# Sheet1.net
KiCad netlist of a schematic drawn in Altium Designer
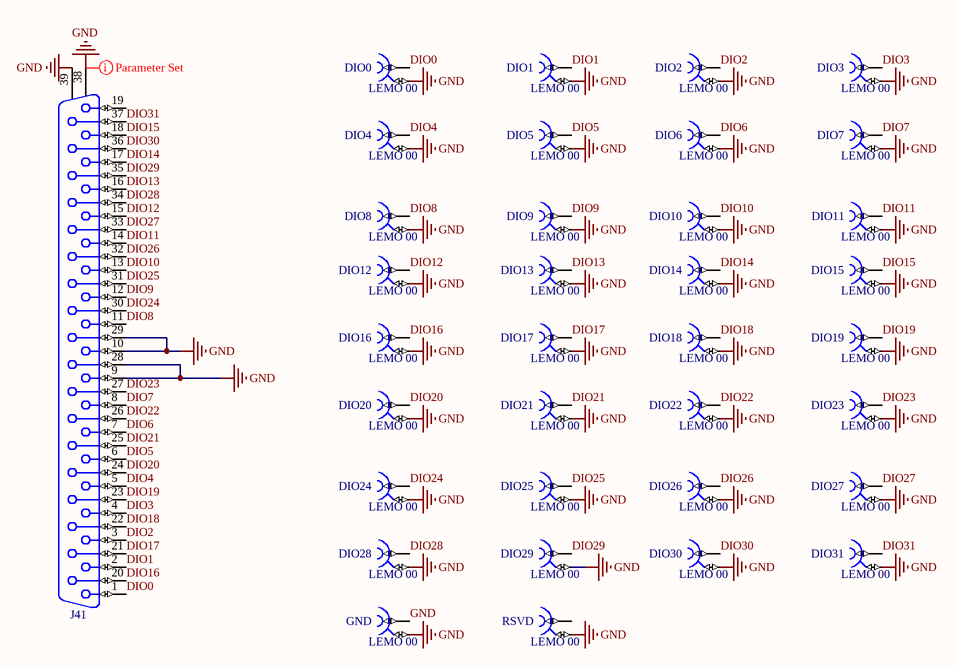
[diagram p0: Sheet1.SchDoc]

(export (version "E")
  (design (tool "Eeschema 10.0.6"))
  (components
    (comp (ref "DIO0")
      (value "LEMO 00")
      (footprint "LEMO_EPA.00.250.NTN")
      (fields
        (field (name "PART NUMBER") "LEMO_EPA.00.250.NTN")
        (field (name "MANUFACTURER") "LEMO")
        (field (name "MANUFACTURER PART NUMBER") "EPA.00.250.NTN")
        (field (name "AUTHOR") "CERN DEM JLC")
      )
      (libsource (lib "Connectors") (part "Coax_1Female_1Shield"))
    )
    (comp (ref "DIO1")
      (value "LEMO 00")
      (footprint "LEMO_EPA.00.250.NTN")
      (fields
        (field (name "PART NUMBER") "LEMO_EPA.00.250.NTN")
        (field (name "MANUFACTURER") "LEMO")
        (field (name "MANUFACTURER PART NUMBER") "EPA.00.250.NTN")
        (field (name "AUTHOR") "CERN DEM JLC")
      )
      (libsource (lib "Connectors") (part "Coax_1Female_1Shield"))
    )
    (comp (ref "DIO2")
      (value "LEMO 00")
      (footprint "LEMO_EPA.00.250.NTN")
      (fields
        (field (name "PART NUMBER") "LEMO_EPA.00.250.NTN")
        (field (name "MANUFACTURER") "LEMO")
        (field (name "MANUFACTURER PART NUMBER") "EPA.00.250.NTN")
        (field (name "AUTHOR") "CERN DEM JLC")
      )
      (libsource (lib "Connectors") (part "Coax_1Female_1Shield"))
    )
    (comp (ref "DIO3")
      (value "LEMO 00")
      (footprint "LEMO_EPA.00.250.NTN")
      (fields
        (field (name "PART NUMBER") "LEMO_EPA.00.250.NTN")
        (field (name "MANUFACTURER") "LEMO")
        (field (name "MANUFACTURER PART NUMBER") "EPA.00.250.NTN")
        (field (name "AUTHOR") "CERN DEM JLC")
      )
      (libsource (lib "Connectors") (part "Coax_1Female_1Shield"))
    )
    (comp (ref "DIO4")
      (value "LEMO 00")
      (footprint "LEMO_EPA.00.250.NTN")
      (fields
        (field (name "PART NUMBER") "LEMO_EPA.00.250.NTN")
        (field (name "MANUFACTURER") "LEMO")
        (field (name "MANUFACTURER PART NUMBER") "EPA.00.250.NTN")
        (field (name "AUTHOR") "CERN DEM JLC")
      )
      (libsource (lib "Connectors") (part "Coax_1Female_1Shield"))
    )
    (comp (ref "DIO5")
      (value "LEMO 00")
      (footprint "LEMO_EPA.00.250.NTN")
      (fields
        (field (name "PART NUMBER") "LEMO_EPA.00.250.NTN")
        (field (name "MANUFACTURER") "LEMO")
        (field (name "MANUFACTURER PART NUMBER") "EPA.00.250.NTN")
        (field (name "AUTHOR") "CERN DEM JLC")
      )
      (libsource (lib "Connectors") (part "Coax_1Female_1Shield"))
    )
    (comp (ref "DIO6")
      (value "LEMO 00")
      (footprint "LEMO_EPA.00.250.NTN")
      (fields
        (field (name "PART NUMBER") "LEMO_EPA.00.250.NTN")
        (field (name "MANUFACTURER") "LEMO")
        (field (name "MANUFACTURER PART NUMBER") "EPA.00.250.NTN")
        (field (name "AUTHOR") "CERN DEM JLC")
      )
      (libsource (lib "Connectors") (part "Coax_1Female_1Shield"))
    )
    (comp (ref "DIO7")
      (value "LEMO 00")
      (footprint "LEMO_EPA.00.250.NTN")
      (fields
        (field (name "PART NUMBER") "LEMO_EPA.00.250.NTN")
        (field (name "MANUFACTURER") "LEMO")
        (field (name "MANUFACTURER PART NUMBER") "EPA.00.250.NTN")
        (field (name "AUTHOR") "CERN DEM JLC")
      )
      (libsource (lib "Connectors") (part "Coax_1Female_1Shield"))
    )
    (comp (ref "DIO8")
      (value "LEMO 00")
      (footprint "LEMO_EPA.00.250.NTN")
      (fields
        (field (name "PART NUMBER") "LEMO_EPA.00.250.NTN")
        (field (name "MANUFACTURER") "LEMO")
        (field (name "MANUFACTURER PART NUMBER") "EPA.00.250.NTN")
        (field (name "AUTHOR") "CERN DEM JLC")
      )
      (libsource (lib "Connectors") (part "Coax_1Female_1Shield"))
    )
    (comp (ref "DIO9")
      (value "LEMO 00")
      (footprint "LEMO_EPA.00.250.NTN")
      (fields
        (field (name "PART NUMBER") "LEMO_EPA.00.250.NTN")
        (field (name "MANUFACTURER") "LEMO")
        (field (name "MANUFACTURER PART NUMBER") "EPA.00.250.NTN")
        (field (name "AUTHOR") "CERN DEM JLC")
      )
      (libsource (lib "Connectors") (part "Coax_1Female_1Shield"))
    )
    (comp (ref "DIO10")
      (value "LEMO 00")
      (footprint "LEMO_EPA.00.250.NTN")
      (fields
        (field (name "PART NUMBER") "LEMO_EPA.00.250.NTN")
        (field (name "MANUFACTURER") "LEMO")
        (field (name "MANUFACTURER PART NUMBER") "EPA.00.250.NTN")
        (field (name "AUTHOR") "CERN DEM JLC")
      )
      (libsource (lib "Connectors") (part "Coax_1Female_1Shield"))
    )
    (comp (ref "DIO11")
      (value "LEMO 00")
      (footprint "LEMO_EPA.00.250.NTN")
      (fields
        (field (name "PART NUMBER") "LEMO_EPA.00.250.NTN")
        (field (name "MANUFACTURER") "LEMO")
        (field (name "MANUFACTURER PART NUMBER") "EPA.00.250.NTN")
        (field (name "AUTHOR") "CERN DEM JLC")
      )
      (libsource (lib "Connectors") (part "Coax_1Female_1Shield"))
    )
    (comp (ref "DIO12")
      (value "LEMO 00")
      (footprint "LEMO_EPA.00.250.NTN")
      (fields
        (field (name "PART NUMBER") "LEMO_EPA.00.250.NTN")
        (field (name "MANUFACTURER") "LEMO")
        (field (name "MANUFACTURER PART NUMBER") "EPA.00.250.NTN")
        (field (name "AUTHOR") "CERN DEM JLC")
      )
      (libsource (lib "Connectors") (part "Coax_1Female_1Shield"))
    )
    (comp (ref "DIO13")
      (value "LEMO 00")
      (footprint "LEMO_EPA.00.250.NTN")
      (fields
        (field (name "PART NUMBER") "LEMO_EPA.00.250.NTN")
        (field (name "MANUFACTURER") "LEMO")
        (field (name "MANUFACTURER PART NUMBER") "EPA.00.250.NTN")
        (field (name "AUTHOR") "CERN DEM JLC")
      )
      (libsource (lib "Connectors") (part "Coax_1Female_1Shield"))
    )
    (comp (ref "DIO14")
      (value "LEMO 00")
      (footprint "LEMO_EPA.00.250.NTN")
      (fields
        (field (name "PART NUMBER") "LEMO_EPA.00.250.NTN")
        (field (name "MANUFACTURER") "LEMO")
        (field (name "MANUFACTURER PART NUMBER") "EPA.00.250.NTN")
        (field (name "AUTHOR") "CERN DEM JLC")
      )
      (libsource (lib "Connectors") (part "Coax_1Female_1Shield"))
    )
    (comp (ref "DIO15")
      (value "LEMO 00")
      (footprint "LEMO_EPA.00.250.NTN")
      (fields
        (field (name "PART NUMBER") "LEMO_EPA.00.250.NTN")
        (field (name "MANUFACTURER") "LEMO")
        (field (name "MANUFACTURER PART NUMBER") "EPA.00.250.NTN")
        (field (name "AUTHOR") "CERN DEM JLC")
      )
      (libsource (lib "Connectors") (part "Coax_1Female_1Shield"))
    )
    (comp (ref "DIO16")
      (value "LEMO 00")
      (footprint "LEMO_EPA.00.250.NTN")
      (fields
        (field (name "PART NUMBER") "LEMO_EPA.00.250.NTN")
        (field (name "MANUFACTURER") "LEMO")
        (field (name "MANUFACTURER PART NUMBER") "EPA.00.250.NTN")
        (field (name "AUTHOR") "CERN DEM JLC")
      )
      (libsource (lib "Connectors") (part "Coax_1Female_1Shield"))
    )
    (comp (ref "DIO17")
      (value "LEMO 00")
      (footprint "LEMO_EPA.00.250.NTN")
      (fields
        (field (name "PART NUMBER") "LEMO_EPA.00.250.NTN")
        (field (name "MANUFACTURER") "LEMO")
        (field (name "MANUFACTURER PART NUMBER") "EPA.00.250.NTN")
        (field (name "AUTHOR") "CERN DEM JLC")
      )
      (libsource (lib "Connectors") (part "Coax_1Female_1Shield"))
    )
    (comp (ref "DIO18")
      (value "LEMO 00")
      (footprint "LEMO_EPA.00.250.NTN")
      (fields
        (field (name "PART NUMBER") "LEMO_EPA.00.250.NTN")
        (field (name "MANUFACTURER") "LEMO")
        (field (name "MANUFACTURER PART NUMBER") "EPA.00.250.NTN")
        (field (name "AUTHOR") "CERN DEM JLC")
      )
      (libsource (lib "Connectors") (part "Coax_1Female_1Shield"))
    )
    (comp (ref "DIO19")
      (value "LEMO 00")
      (footprint "LEMO_EPA.00.250.NTN")
      (fields
        (field (name "PART NUMBER") "LEMO_EPA.00.250.NTN")
        (field (name "MANUFACTURER") "LEMO")
        (field (name "MANUFACTURER PART NUMBER") "EPA.00.250.NTN")
        (field (name "AUTHOR") "CERN DEM JLC")
      )
      (libsource (lib "Connectors") (part "Coax_1Female_1Shield"))
    )
    (comp (ref "DIO20")
      (value "LEMO 00")
      (footprint "LEMO_EPA.00.250.NTN")
      (fields
        (field (name "PART NUMBER") "LEMO_EPA.00.250.NTN")
        (field (name "MANUFACTURER") "LEMO")
        (field (name "MANUFACTURER PART NUMBER") "EPA.00.250.NTN")
        (field (name "AUTHOR") "CERN DEM JLC")
      )
      (libsource (lib "Connectors") (part "Coax_1Female_1Shield"))
    )
    (comp (ref "DIO21")
      (value "LEMO 00")
      (footprint "LEMO_EPA.00.250.NTN")
      (fields
        (field (name "PART NUMBER") "LEMO_EPA.00.250.NTN")
        (field (name "MANUFACTURER") "LEMO")
        (field (name "MANUFACTURER PART NUMBER") "EPA.00.250.NTN")
        (field (name "AUTHOR") "CERN DEM JLC")
      )
      (libsource (lib "Connectors") (part "Coax_1Female_1Shield"))
    )
    (comp (ref "DIO22")
      (value "LEMO 00")
      (footprint "LEMO_EPA.00.250.NTN")
      (fields
        (field (name "PART NUMBER") "LEMO_EPA.00.250.NTN")
        (field (name "MANUFACTURER") "LEMO")
        (field (name "MANUFACTURER PART NUMBER") "EPA.00.250.NTN")
        (field (name "AUTHOR") "CERN DEM JLC")
      )
      (libsource (lib "Connectors") (part "Coax_1Female_1Shield"))
    )
    (comp (ref "DIO23")
      (value "LEMO 00")
      (footprint "LEMO_EPA.00.250.NTN")
      (fields
        (field (name "PART NUMBER") "LEMO_EPA.00.250.NTN")
        (field (name "MANUFACTURER") "LEMO")
        (field (name "MANUFACTURER PART NUMBER") "EPA.00.250.NTN")
        (field (name "AUTHOR") "CERN DEM JLC")
      )
      (libsource (lib "Connectors") (part "Coax_1Female_1Shield"))
    )
    (comp (ref "DIO24")
      (value "LEMO 00")
      (footprint "LEMO_EPA.00.250.NTN")
      (fields
        (field (name "PART NUMBER") "LEMO_EPA.00.250.NTN")
        (field (name "MANUFACTURER") "LEMO")
        (field (name "MANUFACTURER PART NUMBER") "EPA.00.250.NTN")
        (field (name "AUTHOR") "CERN DEM JLC")
      )
      (libsource (lib "Connectors") (part "Coax_1Female_1Shield"))
    )
    (comp (ref "DIO25")
      (value "LEMO 00")
      (footprint "LEMO_EPA.00.250.NTN")
      (fields
        (field (name "PART NUMBER") "LEMO_EPA.00.250.NTN")
        (field (name "MANUFACTURER") "LEMO")
        (field (name "MANUFACTURER PART NUMBER") "EPA.00.250.NTN")
        (field (name "AUTHOR") "CERN DEM JLC")
      )
      (libsource (lib "Connectors") (part "Coax_1Female_1Shield"))
    )
    (comp (ref "DIO26")
      (value "LEMO 00")
      (footprint "LEMO_EPA.00.250.NTN")
      (fields
        (field (name "PART NUMBER") "LEMO_EPA.00.250.NTN")
        (field (name "MANUFACTURER") "LEMO")
        (field (name "MANUFACTURER PART NUMBER") "EPA.00.250.NTN")
        (field (name "AUTHOR") "CERN DEM JLC")
      )
      (libsource (lib "Connectors") (part "Coax_1Female_1Shield"))
    )
    (comp (ref "DIO27")
      (value "LEMO 00")
      (footprint "LEMO_EPA.00.250.NTN")
      (fields
        (field (name "PART NUMBER") "LEMO_EPA.00.250.NTN")
        (field (name "MANUFACTURER") "LEMO")
        (field (name "MANUFACTURER PART NUMBER") "EPA.00.250.NTN")
        (field (name "AUTHOR") "CERN DEM JLC")
      )
      (libsource (lib "Connectors") (part "Coax_1Female_1Shield"))
    )
    (comp (ref "DIO28")
      (value "LEMO 00")
      (footprint "LEMO_EPA.00.250.NTN")
      (fields
        (field (name "PART NUMBER") "LEMO_EPA.00.250.NTN")
        (field (name "MANUFACTURER") "LEMO")
        (field (name "MANUFACTURER PART NUMBER") "EPA.00.250.NTN")
        (field (name "AUTHOR") "CERN DEM JLC")
      )
      (libsource (lib "Connectors") (part "Coax_1Female_1Shield"))
    )
    (comp (ref "DIO29")
      (value "LEMO 00")
      (footprint "LEMO_EPA.00.250.NTN")
      (fields
        (field (name "PART NUMBER") "LEMO_EPA.00.250.NTN")
        (field (name "MANUFACTURER") "LEMO")
        (field (name "MANUFACTURER PART NUMBER") "EPA.00.250.NTN")
        (field (name "AUTHOR") "CERN DEM JLC")
      )
      (libsource (lib "Connectors") (part "Coax_1Female_1Shield"))
    )
    (comp (ref "DIO30")
      (value "LEMO 00")
      (footprint "LEMO_EPA.00.250.NTN")
      (fields
        (field (name "PART NUMBER") "LEMO_EPA.00.250.NTN")
        (field (name "MANUFACTURER") "LEMO")
        (field (name "MANUFACTURER PART NUMBER") "EPA.00.250.NTN")
        (field (name "AUTHOR") "CERN DEM JLC")
      )
      (libsource (lib "Connectors") (part "Coax_1Female_1Shield"))
    )
    (comp (ref "DIO31")
      (value "LEMO 00")
      (footprint "LEMO_EPA.00.250.NTN")
      (fields
        (field (name "PART NUMBER") "LEMO_EPA.00.250.NTN")
        (field (name "MANUFACTURER") "LEMO")
        (field (name "MANUFACTURER PART NUMBER") "EPA.00.250.NTN")
        (field (name "AUTHOR") "CERN DEM JLC")
      )
      (libsource (lib "Connectors") (part "Coax_1Female_1Shield"))
    )
    (comp (ref "GND")
      (value "LEMO 00")
      (footprint "LEMO_EPA.00.250.NTN")
      (fields
        (field (name "PART NUMBER") "LEMO_EPA.00.250.NTN")
        (field (name "MANUFACTURER") "LEMO")
        (field (name "MANUFACTURER PART NUMBER") "EPA.00.250.NTN")
        (field (name "AUTHOR") "CERN DEM JLC")
      )
      (libsource (lib "Connectors") (part "Coax_1Female_1Shield"))
    )
    (comp (ref "J41")
      (value "D-SUB37F")
      (footprint "NORCOMP_172-037-242R011")
      (description "Connector D-sub 37 Female")
      (fields
        (field (name "PART NUMBER") "NORCOMP_172-037-242R011")
        (field (name "MANUFACTURER") "NORCOMP")
        (field (name "AUTHOR") "CERN DEM MR")
      )
      (libsource (lib "Connectors") (part "Connector D-sub 37 Female"))
    )
    (comp (ref "RSVD")
      (value "LEMO 00")
      (footprint "LEMO_EPA.00.250.NTN")
      (fields
        (field (name "PART NUMBER") "LEMO_EPA.00.250.NTN")
        (field (name "MANUFACTURER") "LEMO")
        (field (name "MANUFACTURER PART NUMBER") "EPA.00.250.NTN")
        (field (name "AUTHOR") "CERN DEM JLC")
      )
      (libsource (lib "Connectors") (part "Coax_1Female_1Shield"))
    )
  )
  (nets
    (net (code "1") (name "/DIO0") (class "Default")
      (node (ref "DIO0") (pin "1") (pinfunction "1_1") (pintype "bidirectional"))
      (node (ref "J41") (pin "1") (pinfunction "1_1") (pintype "bidirectional"))
    )
    (net (code "2") (name "/DIO1") (class "Default")
      (node (ref "DIO1") (pin "1") (pinfunction "1_1") (pintype "bidirectional"))
      (node (ref "J41") (pin "2") (pinfunction "2_2") (pintype "bidirectional"))
    )
    (net (code "3") (name "/DIO2") (class "Default")
      (node (ref "DIO2") (pin "1") (pinfunction "1_1") (pintype "bidirectional"))
      (node (ref "J41") (pin "3") (pinfunction "3_3") (pintype "bidirectional"))
    )
    (net (code "4") (name "/DIO3") (class "Default")
      (node (ref "DIO3") (pin "1") (pinfunction "1_1") (pintype "bidirectional"))
      (node (ref "J41") (pin "4") (pinfunction "4_4") (pintype "bidirectional"))
    )
    (net (code "5") (name "/DIO4") (class "Default")
      (node (ref "DIO4") (pin "1") (pinfunction "1_1") (pintype "bidirectional"))
      (node (ref "J41") (pin "5") (pinfunction "5_5") (pintype "bidirectional"))
    )
    (net (code "6") (name "/DIO5") (class "Default")
      (node (ref "DIO5") (pin "1") (pinfunction "1_1") (pintype "bidirectional"))
      (node (ref "J41") (pin "6") (pinfunction "6_6") (pintype "bidirectional"))
    )
    (net (code "7") (name "/DIO6") (class "Default")
      (node (ref "DIO6") (pin "1") (pinfunction "1_1") (pintype "bidirectional"))
      (node (ref "J41") (pin "7") (pinfunction "7_7") (pintype "bidirectional"))
    )
    (net (code "8") (name "/DIO7") (class "Default")
      (node (ref "DIO7") (pin "1") (pinfunction "1_1") (pintype "bidirectional"))
      (node (ref "J41") (pin "8") (pinfunction "8_8") (pintype "bidirectional"))
    )
    (net (code "9") (name "/DIO8") (class "Default")
      (node (ref "DIO8") (pin "1") (pinfunction "1_1") (pintype "bidirectional"))
      (node (ref "J41") (pin "11") (pinfunction "11_11") (pintype "bidirectional"))
    )
    (net (code "10") (name "/DIO9") (class "Default")
      (node (ref "DIO9") (pin "1") (pinfunction "1_1") (pintype "bidirectional"))
      (node (ref "J41") (pin "12") (pinfunction "12_12") (pintype "bidirectional"))
    )
    (net (code "11") (name "/DIO10") (class "Default")
      (node (ref "DIO10") (pin "1") (pinfunction "1_1") (pintype "bidirectional"))
      (node (ref "J41") (pin "13") (pinfunction "13_13") (pintype "bidirectional"))
    )
    (net (code "12") (name "/DIO11") (class "Default")
      (node (ref "DIO11") (pin "1") (pinfunction "1_1") (pintype "bidirectional"))
      (node (ref "J41") (pin "14") (pinfunction "14_14") (pintype "bidirectional"))
    )
    (net (code "13") (name "/DIO12") (class "Default")
      (node (ref "DIO12") (pin "1") (pinfunction "1_1") (pintype "bidirectional"))
      (node (ref "J41") (pin "15") (pinfunction "15_15") (pintype "bidirectional"))
    )
    (net (code "14") (name "/DIO13") (class "Default")
      (node (ref "DIO13") (pin "1") (pinfunction "1_1") (pintype "bidirectional"))
      (node (ref "J41") (pin "16") (pinfunction "16_16") (pintype "bidirectional"))
    )
    (net (code "15") (name "/DIO14") (class "Default")
      (node (ref "DIO14") (pin "1") (pinfunction "1_1") (pintype "bidirectional"))
      (node (ref "J41") (pin "17") (pinfunction "17_17") (pintype "bidirectional"))
    )
    (net (code "16") (name "/DIO15") (class "Default")
      (node (ref "DIO15") (pin "1") (pinfunction "1_1") (pintype "bidirectional"))
      (node (ref "J41") (pin "18") (pinfunction "18_18") (pintype "bidirectional"))
    )
    (net (code "17") (name "/DIO16") (class "Default")
      (node (ref "DIO16") (pin "1") (pinfunction "1_1") (pintype "bidirectional"))
      (node (ref "J41") (pin "20") (pinfunction "20_20") (pintype "bidirectional"))
    )
    (net (code "18") (name "/DIO17") (class "Default")
      (node (ref "DIO17") (pin "1") (pinfunction "1_1") (pintype "bidirectional"))
      (node (ref "J41") (pin "21") (pinfunction "21_21") (pintype "bidirectional"))
    )
    (net (code "19") (name "/DIO18") (class "Default")
      (node (ref "DIO18") (pin "1") (pinfunction "1_1") (pintype "bidirectional"))
      (node (ref "J41") (pin "22") (pinfunction "22_22") (pintype "bidirectional"))
    )
    (net (code "20") (name "/DIO19") (class "Default")
      (node (ref "DIO19") (pin "1") (pinfunction "1_1") (pintype "bidirectional"))
      (node (ref "J41") (pin "23") (pinfunction "23_23") (pintype "bidirectional"))
    )
    (net (code "21") (name "/DIO20") (class "Default")
      (node (ref "DIO20") (pin "1") (pinfunction "1_1") (pintype "bidirectional"))
      (node (ref "J41") (pin "24") (pinfunction "24_24") (pintype "bidirectional"))
    )
    (net (code "22") (name "/DIO21") (class "Default")
      (node (ref "DIO21") (pin "1") (pinfunction "1_1") (pintype "bidirectional"))
      (node (ref "J41") (pin "25") (pinfunction "25_25") (pintype "bidirectional"))
    )
    (net (code "23") (name "/DIO22") (class "Default")
      (node (ref "DIO22") (pin "1") (pinfunction "1_1") (pintype "bidirectional"))
      (node (ref "J41") (pin "26") (pinfunction "26_26") (pintype "bidirectional"))
    )
    (net (code "24") (name "/DIO23") (class "Default")
      (node (ref "DIO23") (pin "1") (pinfunction "1_1") (pintype "bidirectional"))
      (node (ref "J41") (pin "27") (pinfunction "27_27") (pintype "bidirectional"))
    )
    (net (code "25") (name "/DIO24") (class "Default")
      (node (ref "DIO24") (pin "1") (pinfunction "1_1") (pintype "bidirectional"))
      (node (ref "J41") (pin "30") (pinfunction "30_30") (pintype "bidirectional"))
    )
    (net (code "26") (name "/DIO25") (class "Default")
      (node (ref "DIO25") (pin "1") (pinfunction "1_1") (pintype "bidirectional"))
      (node (ref "J41") (pin "31") (pinfunction "31_31") (pintype "bidirectional"))
    )
    (net (code "27") (name "/DIO26") (class "Default")
      (node (ref "DIO26") (pin "1") (pinfunction "1_1") (pintype "bidirectional"))
      (node (ref "J41") (pin "32") (pinfunction "32_32") (pintype "bidirectional"))
    )
    (net (code "28") (name "/DIO27") (class "Default")
      (node (ref "DIO27") (pin "1") (pinfunction "1_1") (pintype "bidirectional"))
      (node (ref "J41") (pin "33") (pinfunction "33_33") (pintype "bidirectional"))
    )
    (net (code "29") (name "/DIO28") (class "Default")
      (node (ref "DIO28") (pin "1") (pinfunction "1_1") (pintype "bidirectional"))
      (node (ref "J41") (pin "34") (pinfunction "34_34") (pintype "bidirectional"))
    )
    (net (code "30") (name "/DIO29") (class "Default")
      (node (ref "DIO29") (pin "1") (pinfunction "1_1") (pintype "bidirectional"))
      (node (ref "J41") (pin "35") (pinfunction "35_35") (pintype "bidirectional"))
    )
    (net (code "31") (name "/DIO30") (class "Default")
      (node (ref "DIO30") (pin "1") (pinfunction "1_1") (pintype "bidirectional"))
      (node (ref "J41") (pin "36") (pinfunction "36_36") (pintype "bidirectional"))
    )
    (net (code "32") (name "/DIO31") (class "Default")
      (node (ref "DIO31") (pin "1") (pinfunction "1_1") (pintype "bidirectional"))
      (node (ref "J41") (pin "37") (pinfunction "37_37") (pintype "bidirectional"))
    )
    (net (code "33") (name "GND") (class "Default")
      (node (ref "DIO0") (pin "2") (pinfunction "2_2") (pintype "bidirectional"))
      (node (ref "DIO1") (pin "2") (pinfunction "2_2") (pintype "bidirectional"))
      (node (ref "DIO10") (pin "2") (pinfunction "2_2") (pintype "bidirectional"))
      (node (ref "DIO11") (pin "2") (pinfunction "2_2") (pintype "bidirectional"))
      (node (ref "DIO12") (pin "2") (pinfunction "2_2") (pintype "bidirectional"))
      (node (ref "DIO13") (pin "2") (pinfunction "2_2") (pintype "bidirectional"))
      (node (ref "DIO14") (pin "2") (pinfunction "2_2") (pintype "bidirectional"))
      (node (ref "DIO15") (pin "2") (pinfunction "2_2") (pintype "bidirectional"))
      (node (ref "DIO16") (pin "2") (pinfunction "2_2") (pintype "bidirectional"))
      (node (ref "DIO17") (pin "2") (pinfunction "2_2") (pintype "bidirectional"))
      (node (ref "DIO18") (pin "2") (pinfunction "2_2") (pintype "bidirectional"))
      (node (ref "DIO19") (pin "2") (pinfunction "2_2") (pintype "bidirectional"))
      (node (ref "DIO2") (pin "2") (pinfunction "2_2") (pintype "bidirectional"))
      (node (ref "DIO20") (pin "2") (pinfunction "2_2") (pintype "bidirectional"))
      (node (ref "DIO21") (pin "2") (pinfunction "2_2") (pintype "bidirectional"))
      (node (ref "DIO22") (pin "2") (pinfunction "2_2") (pintype "bidirectional"))
      (node (ref "DIO23") (pin "2") (pinfunction "2_2") (pintype "bidirectional"))
      (node (ref "DIO24") (pin "2") (pinfunction "2_2") (pintype "bidirectional"))
      (node (ref "DIO25") (pin "2") (pinfunction "2_2") (pintype "bidirectional"))
      (node (ref "DIO26") (pin "2") (pinfunction "2_2") (pintype "bidirectional"))
      (node (ref "DIO27") (pin "2") (pinfunction "2_2") (pintype "bidirectional"))
      (node (ref "DIO28") (pin "2") (pinfunction "2_2") (pintype "bidirectional"))
      (node (ref "DIO29") (pin "2") (pinfunction "2_2") (pintype "bidirectional"))
      (node (ref "DIO3") (pin "2") (pinfunction "2_2") (pintype "bidirectional"))
      (node (ref "DIO30") (pin "2") (pinfunction "2_2") (pintype "bidirectional"))
      (node (ref "DIO31") (pin "2") (pinfunction "2_2") (pintype "bidirectional"))
      (node (ref "DIO4") (pin "2") (pinfunction "2_2") (pintype "bidirectional"))
      (node (ref "DIO5") (pin "2") (pinfunction "2_2") (pintype "bidirectional"))
      (node (ref "DIO6") (pin "2") (pinfunction "2_2") (pintype "bidirectional"))
      (node (ref "DIO7") (pin "2") (pinfunction "2_2") (pintype "bidirectional"))
      (node (ref "DIO8") (pin "2") (pinfunction "2_2") (pintype "bidirectional"))
      (node (ref "DIO9") (pin "2") (pinfunction "2_2") (pintype "bidirectional"))
      (node (ref "GND") (pin "1") (pinfunction "1_1") (pintype "bidirectional"))
      (node (ref "GND") (pin "2") (pinfunction "2_2") (pintype "bidirectional"))
      (node (ref "J41") (pin "10") (pinfunction "10_10") (pintype "bidirectional"))
      (node (ref "J41") (pin "28") (pinfunction "28_28") (pintype "bidirectional"))
      (node (ref "J41") (pin "29") (pinfunction "29_29") (pintype "bidirectional"))
      (node (ref "J41") (pin "38") (pinfunction "38_38") (pintype "passive"))
      (node (ref "J41") (pin "39") (pinfunction "39_39") (pintype "passive"))
      (node (ref "J41") (pin "9") (pinfunction "9_9") (pintype "bidirectional"))
      (node (ref "RSVD") (pin "2") (pinfunction "2_2") (pintype "bidirectional"))
    )
    (net (code "34") (name "unconnected-(J41-Pad19)") (class "Default")
      (node (ref "J41") (pin "19") (pinfunction "19_19") (pintype "bidirectional"))
    )
    (net (code "35") (name "unconnected-(RSVD-Pad1)") (class "Default")
      (node (ref "RSVD") (pin "1") (pinfunction "1_1") (pintype "bidirectional"))
    )
  )
)
